# Sensor.net
KiCad netlist of a schematic drawn in Altium Designer
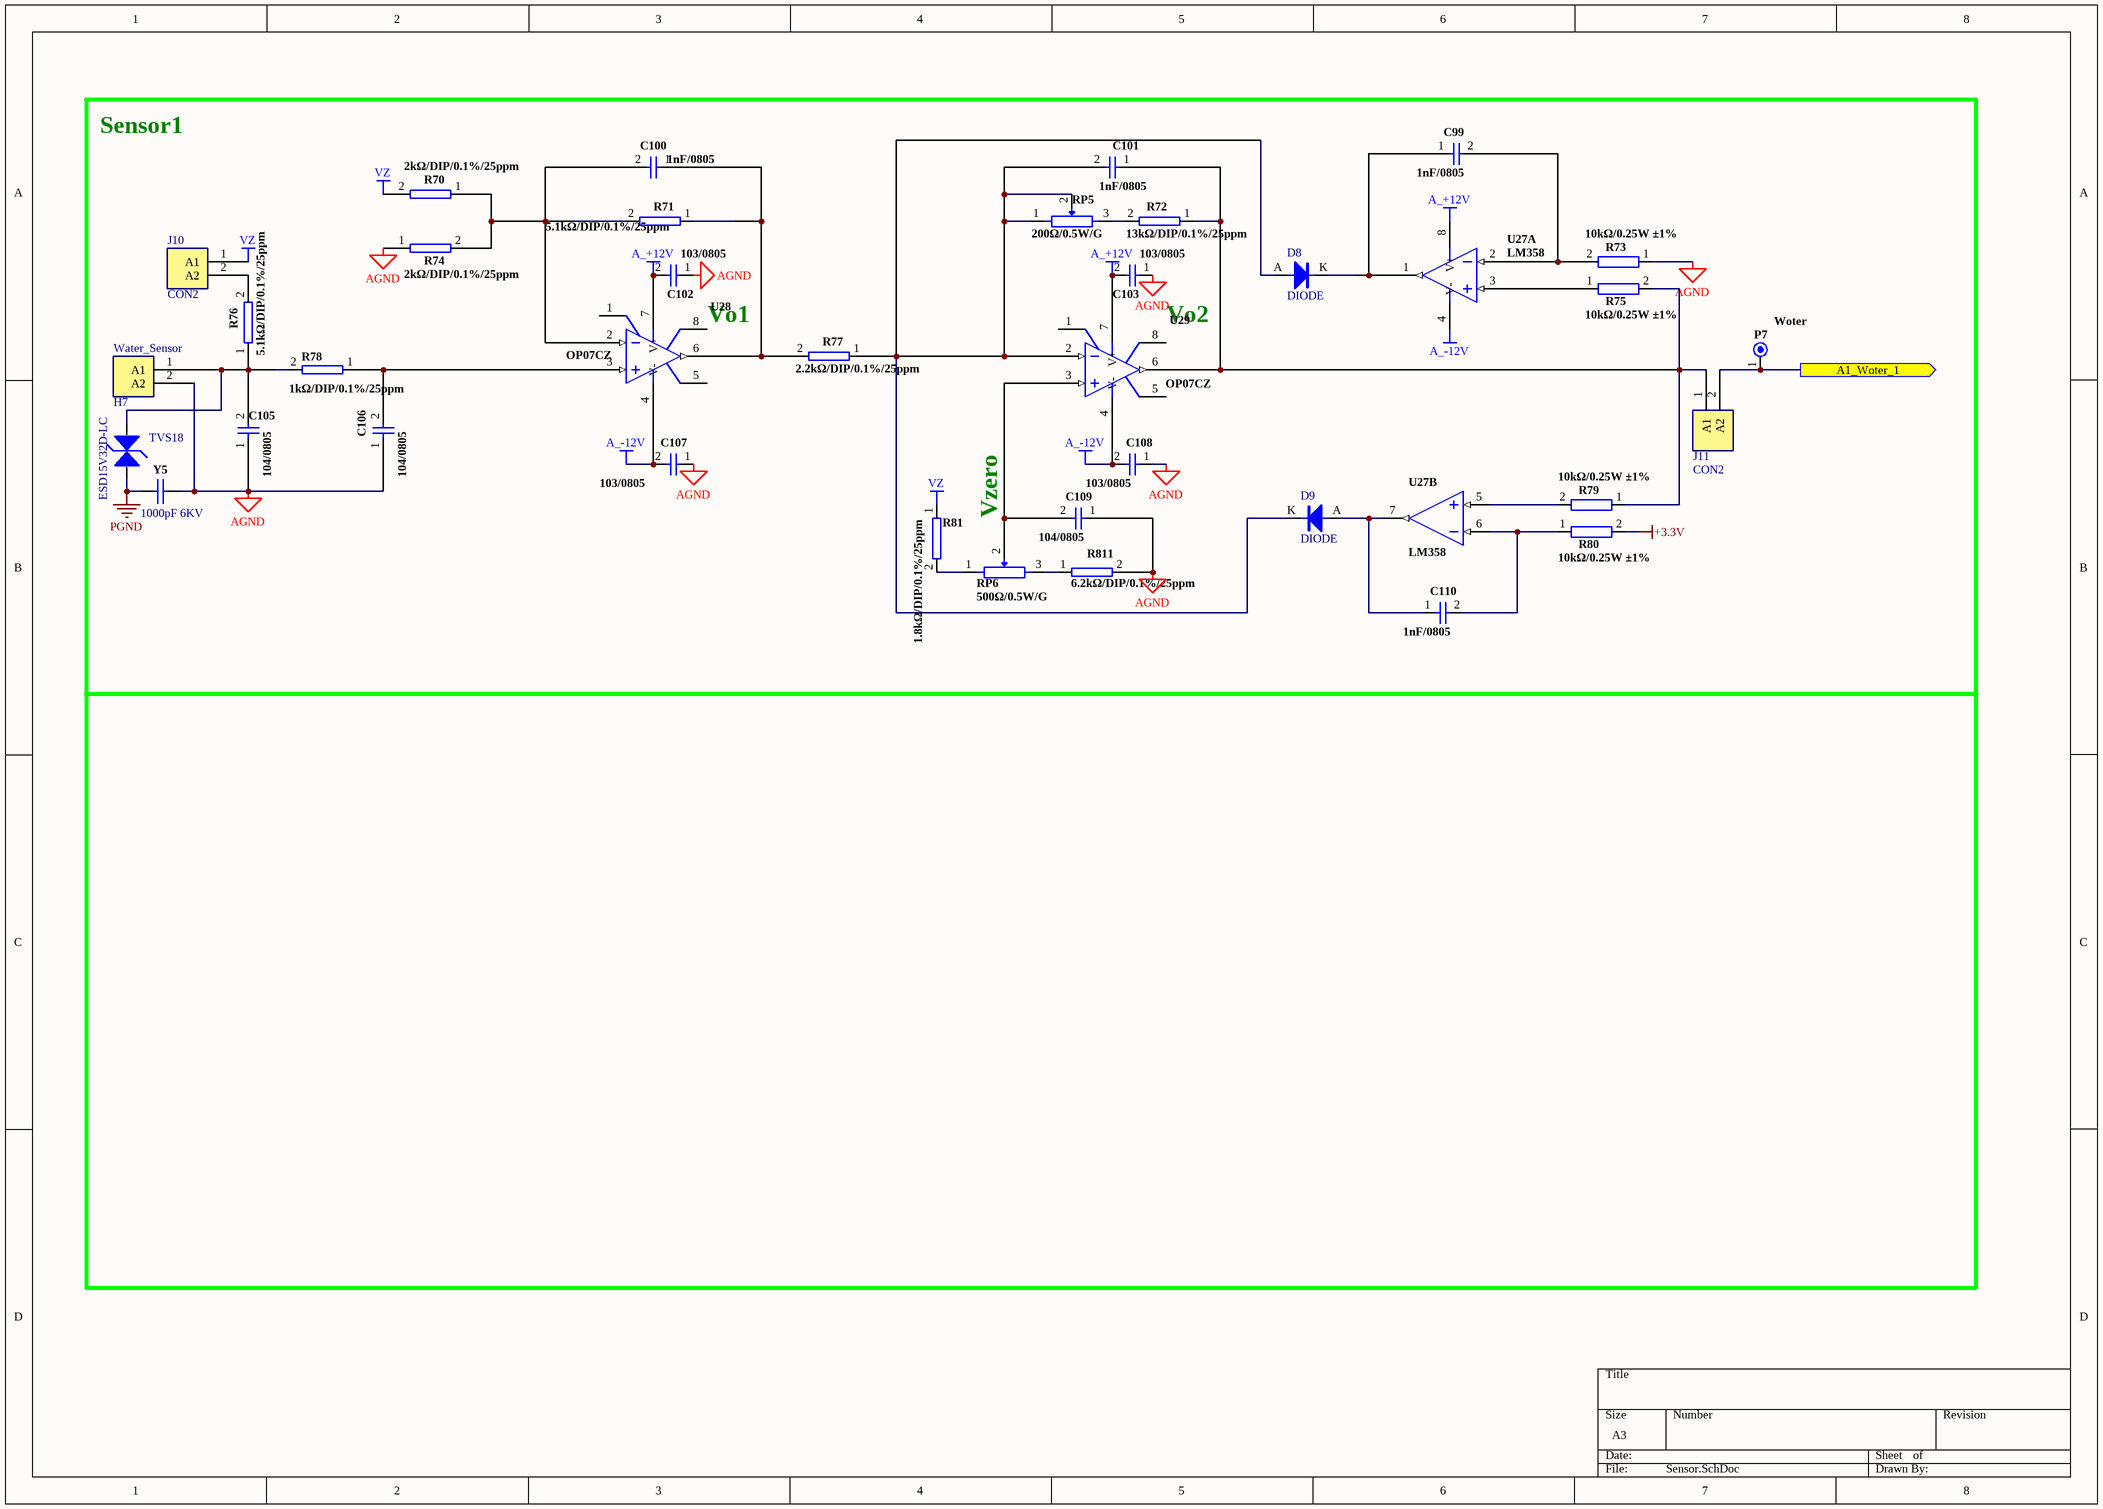
[diagram p0: Sensor.SchDoc]

(export (version "E")
  (design (tool "Eeschema 10.0.6"))
  (components
    (comp (ref "C99")
      (value "1nF/0805")
      (footprint "C0805")
      (description "贴片电容 1nF/25V ±1% C0805")
      (libsource (lib "COOLCONTROL") (part "CAP"))
    )
    (comp (ref "C100")
      (value "1nF/0805")
      (footprint "C0805")
      (description "贴片电容 1nF/25V ±1% C0805")
      (libsource (lib "COOLCONTROL") (part "CAP"))
    )
    (comp (ref "C101")
      (value "1nF/0805")
      (footprint "C0805")
      (description "贴片电容 1nF/25V ±1% C0805")
      (libsource (lib "COOLCONTROL") (part "CAP"))
    )
    (comp (ref "C102")
      (value "103/0805")
      (footprint "C0805")
      (description "贴片电容 103/25V ±1% C0805")
      (libsource (lib "COOLCONTROL") (part "CAP"))
    )
    (comp (ref "C103")
      (value "103/0805")
      (footprint "C0805")
      (description "贴片电容 103/25V ±1% C0805")
      (libsource (lib "COOLCONTROL") (part "CAP"))
    )
    (comp (ref "C105")
      (value "104/0805")
      (footprint "C0805")
      (description "贴片电容 104/25V ±1% C0805")
      (libsource (lib "COOLCONTROL") (part "CAP"))
    )
    (comp (ref "C106")
      (value "104/0805")
      (footprint "C0805")
      (description "贴片电容 104/25V ±1% C0805")
      (libsource (lib "COOLCONTROL") (part "CAP"))
    )
    (comp (ref "C107")
      (value "103/0805")
      (footprint "C0805")
      (description "贴片电容 103/25V ±1% C0805")
      (libsource (lib "COOLCONTROL") (part "CAP"))
    )
    (comp (ref "C108")
      (value "103/0805")
      (footprint "C0805")
      (description "贴片电容 103/25V ±1% C0805")
      (libsource (lib "COOLCONTROL") (part "CAP"))
    )
    (comp (ref "C109")
      (value "104/0805")
      (footprint "C0805")
      (description "贴片电容 104/25V ±1% C0805")
      (libsource (lib "COOLCONTROL") (part "CAP"))
    )
    (comp (ref "C110")
      (value "1nF/0805")
      (footprint "C0805")
      (description "贴片电容 1nF/25V ±1% C0805")
      (libsource (lib "COOLCONTROL") (part "CAP"))
    )
    (comp (ref "D8")
      (value "DIODE")
      (footprint "SOD123")
      (description "高速开关二极管 IN4148 1V 150mA SOD123")
      (libsource (lib "COOLCONTROL") (part "DIODE"))
    )
    (comp (ref "D9")
      (value "DIODE")
      (footprint "SOD123")
      (description "高速开关二极管 IN4148 1V 150mA SOD123")
      (libsource (lib "") (part "DIODE_1"))
    )
    (comp (ref "H7")
      (value "Water_Sensor")
      (footprint "XH2")
      (description "插座式端子 XH2.54-2P 250V(DC/AC) 3A")
      (libsource (lib "COOLCONTROL") (part "CON2"))
    )
    (comp (ref "J10")
      (value "CON2")
      (footprint "2Pin-2.54")
      (description "单排排针（2针）2.54mm 2Pin-2.54")
      (libsource (lib "COOLCONTROL") (part "CON2"))
    )
    (comp (ref "J11")
      (value "CON2")
      (footprint "2Pin-2.54")
      (description "单排排针（2针）2.54mm 2Pin-2.54")
      (libsource (lib "") (part "CON2_1"))
    )
    (comp (ref "P7")
      (value "Woter")
      (footprint "COOLCONTROL:TESTSMD")
      (description "测试点")
      (libsource (lib "COOLCONTROL") (part "CON1"))
    )
    (comp (ref "R70")
      (value "2kΩ/DIP/0.1%/25ppm")
      (footprint "AXIAL0.4")
      (description "高精度电阻 2kΩ DIP 0.25W ±0.1% 25ppm AXIAL0.4")
      (libsource (lib "") (part "RES2_1"))
    )
    (comp (ref "R71")
      (value "5.1kΩ/DIP/0.1%/25ppm")
      (footprint "AXIAL0.4")
      (description "高精度电阻 5.1kΩ DIP 0.25W ±0.1% 25ppm AXIAL0.4")
      (libsource (lib "") (part "RES2_1"))
    )
    (comp (ref "R72")
      (value "13kΩ/DIP/0.1%/25ppm")
      (footprint "COOLCONTROL:AXIAL0.4")
      (description "高精度电阻 13kΩ DIP 0.25W ±0.1% 25ppm AXIAL0.4")
      (libsource (lib "") (part "RES2_1"))
    )
    (comp (ref "R73")
      (value "10kΩ/0.25W ±1%")
      (footprint "R0805")
      (description "贴片电阻 10kΩ 0.25W ±1% R0805")
      (libsource (lib "COOLCONTROL") (part "RES2"))
    )
    (comp (ref "R74")
      (value "2kΩ/DIP/0.1%/25ppm")
      (footprint "AXIAL0.4")
      (description "高精度电阻 2kΩ DIP 0.25W ±0.1% 25ppm AXIAL0.4")
      (libsource (lib "") (part "RES2_1"))
    )
    (comp (ref "R75")
      (value "10kΩ/0.25W ±1%")
      (footprint "R0805")
      (description "贴片电阻 10kΩ 0.25W ±1% R0805")
      (libsource (lib "") (part "RES2_2"))
    )
    (comp (ref "R76")
      (value "5.1kΩ/DIP/0.1%/25ppm")
      (footprint "AXIAL0.4")
      (description "高精度电阻 5.1kΩ DIP 0.25W ±0.1% 25ppm AXIAL0.4")
      (libsource (lib "") (part "RES2_1"))
    )
    (comp (ref "R77")
      (value "2.2kΩ/DIP/0.1%/25ppm")
      (footprint "COOLCONTROL:AXIAL0.4")
      (description "高精度电阻 2.2kΩ DIP 0.25W ±0.1% 25ppm AXIAL0.4")
      (libsource (lib "") (part "RES2_1"))
    )
    (comp (ref "R78")
      (value "1kΩ/DIP/0.1%/25ppm")
      (footprint "AXIAL0.4")
      (description "高精度电阻 1kΩ DIP 0.25W ±0.1% 25ppm AXIAL0.4")
      (libsource (lib "") (part "RES2_1"))
    )
    (comp (ref "R79")
      (value "10kΩ/0.25W ±1%")
      (footprint "R0805")
      (description "贴片电阻 10kΩ 0.25W ±1% R0805")
      (libsource (lib "COOLCONTROL") (part "RES2"))
    )
    (comp (ref "R80")
      (value "10kΩ/0.25W ±1%")
      (footprint "R0805")
      (description "贴片电阻 10kΩ 0.25W ±1% R0805")
      (libsource (lib "") (part "RES2_2"))
    )
    (comp (ref "R81")
      (value "1.8kΩ/DIP/0.1%/25ppm")
      (footprint "COOLCONTROL:AXIAL0.4")
      (description "高精度电阻 1.8kΩ 0.25W ±0.1% 25ppm AXIAL0.4")
      (libsource (lib "") (part "RES2_1"))
    )
    (comp (ref "R811")
      (value "6.2kΩ/DIP/0.1%/25ppm")
      (footprint "COOLCONTROL:AXIAL0.4")
      (description "高精度电阻 6.2kΩ DIP 0.25W ±0.1% 25ppm AXIAL0.4")
      (libsource (lib "") (part "RES2_1"))
    )
    (comp (ref "RP5")
      (value "200Ω/0.5W/G")
      (footprint "3224W")
      (description "高精密可调电位器 200Ω/0.5W/G 3224W")
      (libsource (lib "COOLCONTROL") (part "RPOT"))
    )
    (comp (ref "RP6")
      (value "500Ω/0.5W/G")
      (footprint "3224W")
      (description "高精密可调电位器 500Ω/0.5W/G 3224W")
      (libsource (lib "COOLCONTROL") (part "RPOT"))
    )
    (comp (ref "TVS18")
      (value "ESD15V32D-LC")
      (footprint "SOD323")
      (description "ESD静电二极管 ESD15V32D-LC 15V 15KV 40A SOD323")
      (libsource (lib "COOLCONTROL") (part "TVS"))
    )
    (comp (ref "U27")
      (value "LM358")
      (footprint "SO-8")
      (description "双运算放大器 LM358 SO-8")
      (libsource (lib "COOLCONTROL") (part "MC1458D"))
    )
    (comp (ref "U28")
      (value "OP07CZ")
      (footprint "SO-8")
      (description "运算放大器 OP07CZ SO-8")
      (libsource (lib "COOLCONTROL") (part "OP07CZ"))
    )
    (comp (ref "U29")
      (value "OP07CZ")
      (footprint "SO-8")
      (description "运算放大器 OP07CZ SO-8")
      (libsource (lib "COOLCONTROL") (part "OP07CZ"))
    )
    (comp (ref "Y5")
      (value "1000pF 6KV")
      (footprint "CY1002")
      (description "安规电容 1000pF 6KV ±20% CY1002")
      (libsource (lib "") (part "CAP_1"))
    )
  )
  (nets
    (net (code "1") (name "+3.3V") (class "Default") (node (ref "R80") (pin "2") (pintype "passive")))
    (net (code "2") (name "/A1_Woter_1") (class "Default")
      (node (ref "J11") (pin "2") (pinfunction "A2_2") (pintype "passive"))
      (node (ref "P7") (pin "1") (pintype "passive"))
    )
    (net (code "3") (name "AGND") (class "Default")
      (node (ref "C102") (pin "1") (pintype "passive"))
      (node (ref "C103") (pin "1") (pintype "passive"))
      (node (ref "C105") (pin "1") (pintype "passive"))
      (node (ref "C106") (pin "1") (pintype "passive"))
      (node (ref "C107") (pin "1") (pintype "passive"))
      (node (ref "C108") (pin "1") (pintype "passive"))
      (node (ref "C109") (pin "1") (pintype "passive"))
      (node (ref "H7") (pin "2") (pinfunction "A2_2") (pintype "passive"))
      (node (ref "R73") (pin "1") (pintype "passive"))
      (node (ref "R74") (pin "1") (pintype "passive"))
      (node (ref "R811") (pin "2") (pintype "passive"))
      (node (ref "Y5") (pin "2") (pinfunction "2_2") (pintype "passive"))
    )
    (net (code "4") (name "A_+12V") (class "Default")
      (node (ref "C102") (pin "2") (pintype "passive"))
      (node (ref "C103") (pin "2") (pintype "passive"))
      (node (ref "U27") (pin "8") (pinfunction "V+_8") (pintype "power_in"))
      (node (ref "U28") (pin "7") (pinfunction "V+_7") (pintype "power_in"))
      (node (ref "U29") (pin "7") (pinfunction "V+_7") (pintype "power_in"))
    )
    (net (code "5") (name "A_-12V") (class "Default")
      (node (ref "C107") (pin "2") (pintype "passive"))
      (node (ref "C108") (pin "2") (pintype "passive"))
      (node (ref "U27") (pin "4") (pinfunction "V-_4") (pintype "power_in"))
      (node (ref "U28") (pin "4") (pinfunction "V-_4") (pintype "power_in"))
      (node (ref "U29") (pin "4") (pinfunction "V-_4") (pintype "power_in"))
    )
    (net (code "6") (name "Net-(C99-Pad1)") (class "Default")
      (node (ref "C99") (pin "1") (pintype "passive"))
      (node (ref "D8") (pin "K") (pinfunction "K_K") (pintype "passive"))
      (node (ref "U27") (pin "1") (pintype "output"))
    )
    (net (code "7") (name "Net-(C99-Pad2)") (class "Default")
      (node (ref "C99") (pin "2") (pintype "passive"))
      (node (ref "R73") (pin "2") (pintype "passive"))
      (node (ref "U27") (pin "2") (pintype "input"))
    )
    (net (code "8") (name "Net-(C100-Pad1)") (class "Default")
      (node (ref "C100") (pin "1") (pintype "passive"))
      (node (ref "R71") (pin "1") (pintype "passive"))
      (node (ref "R77") (pin "2") (pintype "passive"))
      (node (ref "U28") (pin "6") (pintype "output"))
    )
    (net (code "9") (name "Net-(C100-Pad2)") (class "Default")
      (node (ref "C100") (pin "2") (pintype "passive"))
      (node (ref "R70") (pin "1") (pintype "passive"))
      (node (ref "R71") (pin "2") (pintype "passive"))
      (node (ref "R74") (pin "2") (pintype "passive"))
      (node (ref "U28") (pin "2") (pintype "input"))
    )
    (net (code "10") (name "Net-(C101-Pad2)") (class "Default")
      (node (ref "C101") (pin "2") (pintype "passive"))
      (node (ref "D8") (pin "A") (pinfunction "A_A") (pintype "passive"))
      (node (ref "D9") (pin "K") (pinfunction "K_K") (pintype "passive"))
      (node (ref "R77") (pin "1") (pintype "passive"))
      (node (ref "RP5") (pin "1") (pintype "passive"))
      (node (ref "RP5") (pin "2") (pintype "passive"))
      (node (ref "U29") (pin "2") (pintype "input"))
    )
    (net (code "11") (name "Net-(C106-Pad2)") (class "Default")
      (node (ref "C106") (pin "2") (pintype "passive"))
      (node (ref "R78") (pin "1") (pintype "passive"))
      (node (ref "U28") (pin "3") (pintype "input"))
    )
    (net (code "12") (name "Net-(C109-Pad2)") (class "Default")
      (node (ref "C109") (pin "2") (pintype "passive"))
      (node (ref "RP6") (pin "2") (pintype "passive"))
      (node (ref "U29") (pin "3") (pintype "input"))
    )
    (net (code "13") (name "Net-(C110-Pad1)") (class "Default")
      (node (ref "C110") (pin "1") (pintype "passive"))
      (node (ref "D9") (pin "A") (pinfunction "A_A") (pintype "passive"))
      (node (ref "U27") (pin "7") (pintype "output"))
    )
    (net (code "14") (name "Net-(C110-Pad2)") (class "Default")
      (node (ref "C110") (pin "2") (pintype "passive"))
      (node (ref "R80") (pin "1") (pintype "passive"))
      (node (ref "U27") (pin "6") (pintype "input"))
    )
    (net (code "15") (name "Net-(H7-A1)") (class "Default")
      (node (ref "C105") (pin "2") (pintype "passive"))
      (node (ref "H7") (pin "1") (pinfunction "A1_1") (pintype "passive"))
      (node (ref "R76") (pin "1") (pintype "passive"))
      (node (ref "R78") (pin "2") (pintype "passive"))
      (node (ref "TVS18") (pin "1") (pinfunction "1_1") (pintype "passive"))
    )
    (net (code "16") (name "Net-(J10-A2)") (class "Default")
      (node (ref "J10") (pin "2") (pinfunction "A2_2") (pintype "passive"))
      (node (ref "R76") (pin "2") (pintype "passive"))
    )
    (net (code "17") (name "Net-(J11-A1)") (class "Default")
      (node (ref "C101") (pin "1") (pintype "passive"))
      (node (ref "J11") (pin "1") (pinfunction "A1_1") (pintype "passive"))
      (node (ref "R72") (pin "1") (pintype "passive"))
      (node (ref "R75") (pin "2") (pintype "passive"))
      (node (ref "R79") (pin "1") (pintype "passive"))
      (node (ref "U29") (pin "6") (pintype "output"))
    )
    (net (code "18") (name "Net-(R72-Pad2)") (class "Default")
      (node (ref "R72") (pin "2") (pintype "passive"))
      (node (ref "RP5") (pin "3") (pintype "passive"))
    )
    (net (code "19") (name "Net-(R75-Pad1)") (class "Default")
      (node (ref "R75") (pin "1") (pintype "passive"))
      (node (ref "U27") (pin "3") (pintype "input"))
    )
    (net (code "20") (name "Net-(R79-Pad2)") (class "Default")
      (node (ref "R79") (pin "2") (pintype "passive"))
      (node (ref "U27") (pin "5") (pintype "input"))
    )
    (net (code "21") (name "Net-(R81-Pad2)") (class "Default")
      (node (ref "R81") (pin "2") (pintype "passive"))
      (node (ref "RP6") (pin "1") (pintype "passive"))
    )
    (net (code "22") (name "Net-(R811-Pad1)") (class "Default")
      (node (ref "R811") (pin "1") (pintype "passive"))
      (node (ref "RP6") (pin "3") (pintype "passive"))
    )
    (net (code "23") (name "PGND") (class "Default")
      (node (ref "TVS18") (pin "2") (pinfunction "2_2") (pintype "passive"))
      (node (ref "Y5") (pin "1") (pinfunction "1_1") (pintype "passive"))
    )
    (net (code "24") (name "VZ") (class "Default")
      (node (ref "J10") (pin "1") (pinfunction "A1_1") (pintype "passive"))
      (node (ref "R70") (pin "2") (pintype "passive"))
      (node (ref "R81") (pin "1") (pintype "passive"))
    )
    (net (code "25") (name "unconnected-(U28-Pad1)") (class "Default")
      (node (ref "U28") (pin "1") (pintype "passive"))
    )
    (net (code "26") (name "unconnected-(U28-Pad5)") (class "Default")
      (node (ref "U28") (pin "5") (pintype "passive"))
    )
    (net (code "27") (name "unconnected-(U28-Pad8)") (class "Default")
      (node (ref "U28") (pin "8") (pintype "passive"))
    )
    (net (code "28") (name "unconnected-(U29-Pad1)") (class "Default")
      (node (ref "U29") (pin "1") (pintype "passive"))
    )
    (net (code "29") (name "unconnected-(U29-Pad5)") (class "Default")
      (node (ref "U29") (pin "5") (pintype "passive"))
    )
    (net (code "30") (name "unconnected-(U29-Pad8)") (class "Default")
      (node (ref "U29") (pin "8") (pintype "passive"))
    )
  )
)
